# XMOD.net
KiCad netlist of a schematic drawn in Altium Designer
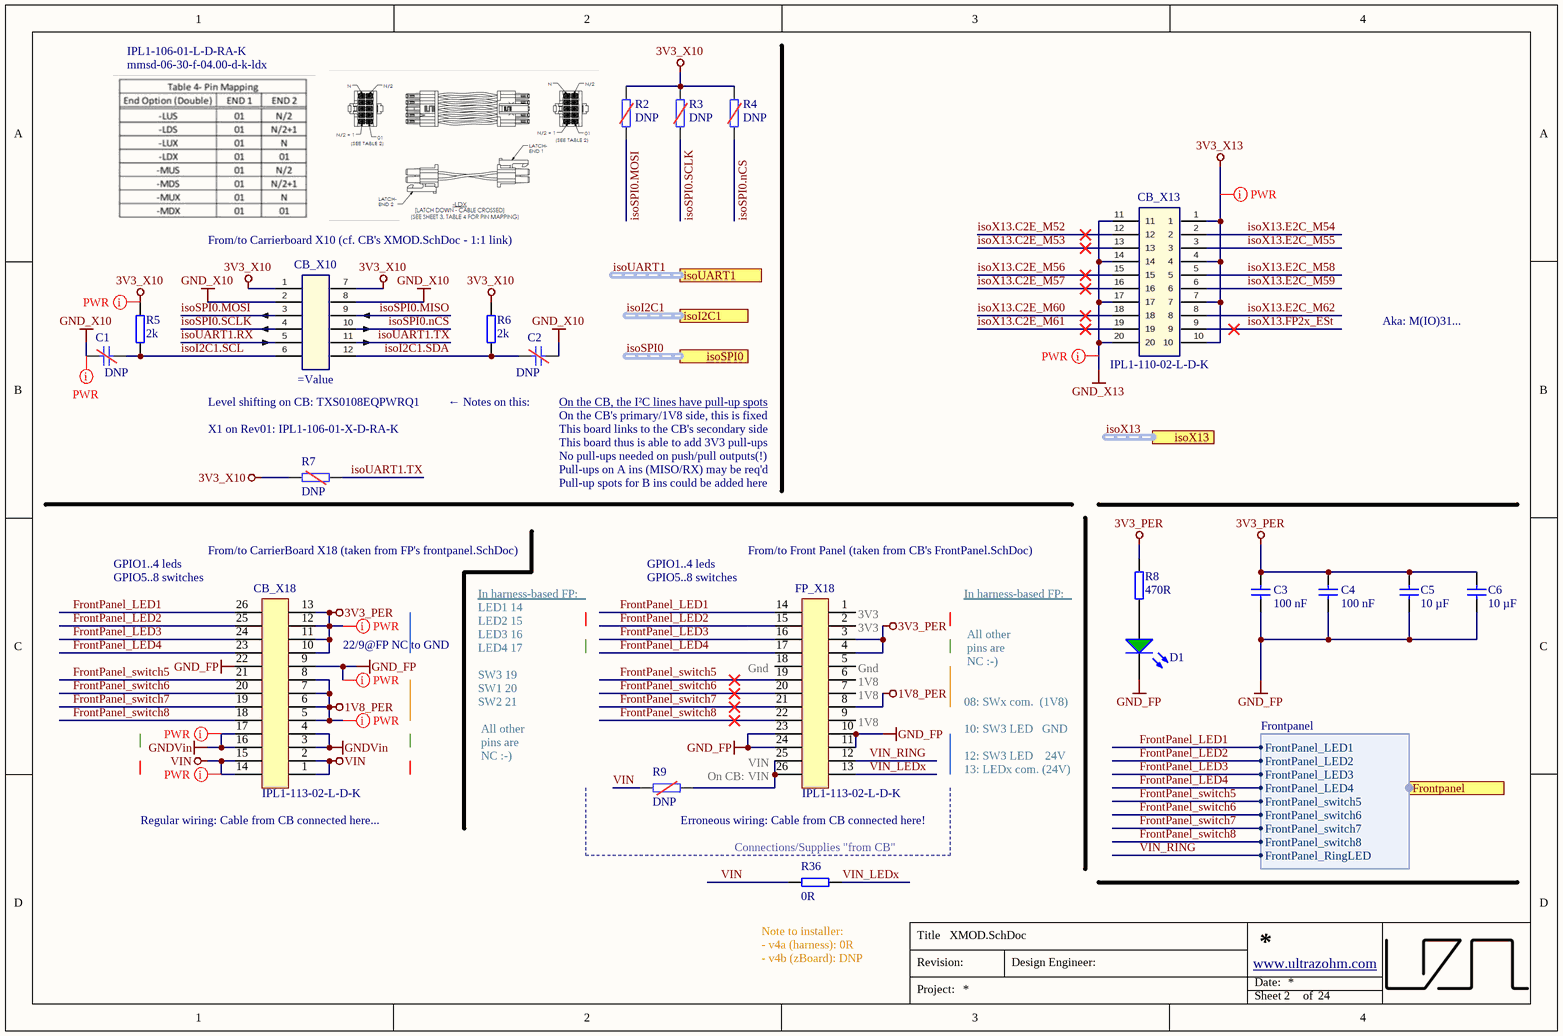
[diagram p0: XMOD.SchDoc]

(export (version "E")
  (design (tool "Eeschema 10.0.6"))
  (components
    (comp (ref "C1")
      (value "DNP")
      (footprint "C_0603_TE-DNP")
      (description "Generic capacitor (DNP)")
      (fields
        (field (name "MANUFACTURER PART NUMBER") "UZgen_C_0603_DNP")
        (field (name "MANUFACTURER") "UZgen")
        (field (name "CREATED FROM") "UZgenTool")
      )
      (libsource (lib "user") (part "CAP-NP-DNP"))
    )
    (comp (ref "C2")
      (value "DNP")
      (footprint "C_0603_TE-DNP")
      (description "Generic capacitor (DNP)")
      (fields
        (field (name "MANUFACTURER PART NUMBER") "UZgen_C_0603_DNP")
        (field (name "MANUFACTURER") "UZgen")
        (field (name "CREATED FROM") "UZgenTool")
      )
      (libsource (lib "user") (part "CAP-NP-DNP"))
    )
    (comp (ref "C3")
      (value "100 nF")
      (footprint "C_0603_TE")
      (description "Generic capacitor")
      (fields
        (field (name "TOLERANCE") "10 %")
        (field (name "MANUFACTURER PART NUMBER") "UZgen_C_0603_100nF_50V_X7R")
        (field (name "CREATED FROM") "AGeiger")
      )
      (libsource (lib "user") (part "CAP-NP"))
    )
    (comp (ref "C4")
      (value "100 nF")
      (footprint "C_0603_TE")
      (description "Generic capacitor")
      (fields
        (field (name "TOLERANCE") "10 %")
        (field (name "MANUFACTURER PART NUMBER") "UZgen_C_0603_100nF_50V_X7R")
        (field (name "CREATED FROM") "AGeiger")
      )
      (libsource (lib "user") (part "CAP-NP"))
    )
    (comp (ref "C5")
      (value "10 µF")
      (footprint "C_1206_TE")
      (description "Generic capacitor")
      (fields
        (field (name "TOLERANCE") "10 %")
        (field (name "VOLTAGE") "50V")
        (field (name "CREATED FROM") "MGeier")
      )
      (libsource (lib "user") (part "CAP-NP"))
    )
    (comp (ref "C6")
      (value "10 µF")
      (footprint "C_1206_TE")
      (description "Generic capacitor")
      (fields
        (field (name "TOLERANCE") "10 %")
        (field (name "VOLTAGE") "50V")
        (field (name "CREATED FROM") "MGeier")
      )
      (libsource (lib "user") (part "CAP-NP"))
    )
    (comp (ref "CB_X10")
      (value "~")
      (footprint "IPL1-106-02-L-D-K")
      (description "Headers & Wire Housings .100\" Mini Mate Isolated Power Terminal Header")
      (fields
        (field (name "MANUFACTURER PART NUMBER") "IPL1-106-02-L-D-K")
        (field (name "MANUFACTURER") "SAMTEC")
        (field (name "CREATED FROM") "AGeiger")
      )
      (libsource (lib "user") (part "IPL1-106-XX-X-D-X"))
    )
    (comp (ref "CB_X13")
      (value "IPL1-110-02-L-D-K")
      (footprint "IPL1-110-02-L-D-K")
      (description "2.54 mm Double Row Termin Assembly (SMD)")
      (fields
        (field (name "MANUFACTURER") "SAMTEC")
        (field (name "LCSC PART NUMBER") "C7544188")
        (field (name "CREATED FROM") "MGremer")
      )
      (libsource (lib "user") (part "IPL1-110-XX-X-D-X"))
    )
    (comp (ref "CB_X18")
      (value "IPL1-113-02-L-D-K")
      (footprint "IPL1-113-02-L-D-K")
      (description "2.54 mm Double Row Termin Assembly (SMD)")
      (fields
        (field (name "MANUFACTURER") "SAMTEC")
        (field (name "LCSC PART NUMBER") "C5290052")
        (field (name "CREATED FROM") "MGremer")
      )
      (libsource (lib "user") (part "IPL1-113-XX-X-D-K"))
    )
    (comp (ref "D1")
      (value "LED Green")
      (footprint "WL-SMCW_0603")
      (description "Standard LEDs - SMD 0603 green")
      (fields
        (field (name "MANUFACTURER PART NUMBER") "UZgen_LED_0603_Green")
        (field (name "MANUFACTURER") "UZgen")
        (field (name "CREATED FROM") "UZgenTool")
      )
      (libsource (lib "user") (part "LED_Green"))
    )
    (comp (ref "FP_X18")
      (value "IPL1-113-02-L-D-K")
      (footprint "IPL1-113-02-L-D-K")
      (description "2.54 mm Double Row Termin Assembly (SMD)")
      (fields
        (field (name "MANUFACTURER") "SAMTEC")
        (field (name "LCSC PART NUMBER") "C5290052")
        (field (name "CREATED FROM") "MGremer")
      )
      (libsource (lib "") (part "IPL1-113-XX-X-D-K_1"))
    )
    (comp (ref "R2")
      (value "DNP")
      (footprint "R_0603_TE-DNP")
      (description "Generic resistor (DNP)")
      (fields
        (field (name "MANUFACTURER PART NUMBER") "UZgen_R_0603_DNP")
        (field (name "MANUFACTURER") "UZgen")
        (field (name "CREATED FROM") "UZgenTool")
      )
      (libsource (lib "user") (part "RES-DNP"))
    )
    (comp (ref "R3")
      (value "DNP")
      (footprint "R_0603_TE-DNP")
      (description "Generic resistor (DNP)")
      (fields
        (field (name "MANUFACTURER PART NUMBER") "UZgen_R_0603_DNP")
        (field (name "MANUFACTURER") "UZgen")
        (field (name "CREATED FROM") "UZgenTool")
      )
      (libsource (lib "user") (part "RES-DNP"))
    )
    (comp (ref "R4")
      (value "DNP")
      (footprint "R_0603_TE-DNP")
      (description "Generic resistor (DNP)")
      (fields
        (field (name "MANUFACTURER PART NUMBER") "UZgen_R_0603_DNP")
        (field (name "MANUFACTURER") "UZgen")
        (field (name "CREATED FROM") "UZgenTool")
      )
      (libsource (lib "user") (part "RES-DNP"))
    )
    (comp (ref "R5")
      (value "2k")
      (footprint "R_0603_TE")
      (description "Generic resistor")
      (fields
        (field (name "TOLERANCE") "1 %")
        (field (name "MANUFACTURER PART NUMBER") "UZgen_R_0603_2k")
        (field (name "CREATED FROM") "UZgenTool")
      )
      (libsource (lib "user") (part "RES"))
    )
    (comp (ref "R6")
      (value "2k")
      (footprint "R_0603_TE")
      (description "Generic resistor")
      (fields
        (field (name "TOLERANCE") "1 %")
        (field (name "MANUFACTURER PART NUMBER") "UZgen_R_0603_2k")
        (field (name "CREATED FROM") "UZgenTool")
      )
      (libsource (lib "user") (part "RES"))
    )
    (comp (ref "R7")
      (value "DNP")
      (footprint "R_0603_TE-DNP")
      (description "Generic resistor (DNP)")
      (fields
        (field (name "MANUFACTURER PART NUMBER") "UZgen_R_0603_DNP")
        (field (name "MANUFACTURER") "UZgen")
        (field (name "CREATED FROM") "UZgenTool")
      )
      (libsource (lib "user") (part "RES-DNP"))
    )
    (comp (ref "R8")
      (value "470R")
      (footprint "R_0603_TE")
      (description "Generic resistor")
      (fields
        (field (name "TOLERANCE") "1 %")
        (field (name "MANUFACTURER PART NUMBER") "UZgen_R_0603_470R")
        (field (name "CREATED FROM") "UZgenTool")
      )
      (libsource (lib "user") (part "RES"))
    )
    (comp (ref "R9")
      (value "DNP")
      (footprint "R_0603_TE-DNP")
      (description "Generic resistor (DNP)")
      (fields
        (field (name "MANUFACTURER PART NUMBER") "UZgen_R_0603_DNP")
        (field (name "MANUFACTURER") "UZgen")
        (field (name "CREATED FROM") "UZgenTool")
      )
      (libsource (lib "user") (part "RES-DNP"))
    )
    (comp (ref "R36")
      (value "0R")
      (footprint "R_0603_TE")
      (description "Generic resistor")
      (fields
        (field (name "TOLERANCE") "1 %")
        (field (name "MANUFACTURER PART NUMBER") "UZgen_R_0603_0R")
        (field (name "CREATED FROM") "UZgenTool")
      )
      (libsource (lib "user") (part "RES"))
    )
  )
  (nets
    (net (code "6") (name "/FrontPanel_LED1") (class "Default")
      (node (ref "CB_X18") (pin "26") (pinfunction "26_26") (pintype "passive"))
      (node (ref "FP_X18") (pin "14") (pinfunction "14_14") (pintype "passive"))
    )
    (net (code "7") (name "/FrontPanel_LED2") (class "Default")
      (node (ref "CB_X18") (pin "25") (pinfunction "25_25") (pintype "passive"))
      (node (ref "FP_X18") (pin "15") (pinfunction "15_15") (pintype "passive"))
    )
    (net (code "8") (name "/FrontPanel_LED3") (class "Default")
      (node (ref "CB_X18") (pin "24") (pinfunction "24_24") (pintype "passive"))
      (node (ref "FP_X18") (pin "16") (pinfunction "16_16") (pintype "passive"))
    )
    (net (code "9") (name "/FrontPanel_LED4") (class "Default")
      (node (ref "CB_X18") (pin "23") (pinfunction "23_23") (pintype "passive"))
      (node (ref "FP_X18") (pin "17") (pinfunction "17_17") (pintype "passive"))
    )
    (net (code "10") (name "/FrontPanel_switch5") (class "Default")
      (node (ref "CB_X18") (pin "21") (pinfunction "21_21") (pintype "passive"))
      (node (ref "FP_X18") (pin "19") (pinfunction "19_19") (pintype "passive"))
    )
    (net (code "11") (name "/FrontPanel_switch6") (class "Default")
      (node (ref "CB_X18") (pin "20") (pinfunction "20_20") (pintype "passive"))
      (node (ref "FP_X18") (pin "20") (pinfunction "20_20") (pintype "passive"))
    )
    (net (code "12") (name "/FrontPanel_switch7") (class "Default")
      (node (ref "CB_X18") (pin "19") (pinfunction "19_19") (pintype "passive"))
      (node (ref "FP_X18") (pin "21") (pinfunction "21_21") (pintype "passive"))
    )
    (net (code "13") (name "/FrontPanel_switch8") (class "Default")
      (node (ref "CB_X18") (pin "18") (pinfunction "18_18") (pintype "passive"))
      (node (ref "FP_X18") (pin "22") (pinfunction "22_22") (pintype "passive"))
    )
    (net (code "14") (name "/VIN_LEDx") (class "Default")
      (node (ref "FP_X18") (pin "13") (pinfunction "13_13") (pintype "passive"))
      (node (ref "R36") (pin "2") (pinfunction "2_2") (pintype "passive"))
    )
    (net (code "15") (name "/VIN_RING") (class "Default")
      (node (ref "FP_X18") (pin "12") (pinfunction "12_12") (pintype "passive"))
    )
    (net (code "16") (name "/isoI2C1.SCL") (class "Default")
      (node (ref "C1") (pin "2") (pinfunction "2_2") (pintype "passive"))
      (node (ref "CB_X10") (pin "6") (pinfunction "6_6") (pintype "passive"))
      (node (ref "R5") (pin "1") (pinfunction "1_1") (pintype "passive"))
    )
    (net (code "17") (name "/isoI2C1.SDA") (class "Default")
      (node (ref "C2") (pin "1") (pinfunction "1_1") (pintype "passive"))
      (node (ref "CB_X10") (pin "12") (pinfunction "12_12") (pintype "passive"))
      (node (ref "R6") (pin "1") (pinfunction "1_1") (pintype "passive"))
    )
    (net (code "18") (name "/isoSPI0.MISO") (class "Default")
      (node (ref "CB_X10") (pin "9") (pinfunction "9_9") (pintype "passive"))
    )
    (net (code "19") (name "/isoSPI0.MOSI") (class "Default")
      (node (ref "CB_X10") (pin "3") (pinfunction "3_3") (pintype "passive"))
      (node (ref "R2") (pin "1") (pinfunction "1_1") (pintype "passive"))
    )
    (net (code "20") (name "/isoSPI0.SCLK") (class "Default")
      (node (ref "CB_X10") (pin "4") (pinfunction "4_4") (pintype "passive"))
      (node (ref "R3") (pin "1") (pinfunction "1_1") (pintype "passive"))
    )
    (net (code "21") (name "/isoSPI0.nCS") (class "Default")
      (node (ref "CB_X10") (pin "10") (pinfunction "10_10") (pintype "passive"))
      (node (ref "R4") (pin "1") (pinfunction "1_1") (pintype "passive"))
    )
    (net (code "22") (name "/isoUART1.RX") (class "Default")
      (node (ref "CB_X10") (pin "5") (pinfunction "5_5") (pintype "passive"))
    )
    (net (code "23") (name "/isoUART1.TX") (class "Default")
      (node (ref "CB_X10") (pin "11") (pinfunction "11_11") (pintype "passive"))
      (node (ref "R7") (pin "1") (pinfunction "1_1") (pintype "passive"))
    )
    (net (code "24") (name "/isoX13.C2E_M52") (class "Default")
      (node (ref "CB_X13") (pin "12") (pinfunction "12_12") (pintype "passive"))
    )
    (net (code "25") (name "/isoX13.C2E_M53") (class "Default")
      (node (ref "CB_X13") (pin "13") (pinfunction "13_13") (pintype "passive"))
    )
    (net (code "26") (name "/isoX13.C2E_M56") (class "Default")
      (node (ref "CB_X13") (pin "15") (pinfunction "15_15") (pintype "passive"))
    )
    (net (code "27") (name "/isoX13.C2E_M57") (class "Default")
      (node (ref "CB_X13") (pin "16") (pinfunction "16_16") (pintype "passive"))
    )
    (net (code "28") (name "/isoX13.C2E_M60") (class "Default")
      (node (ref "CB_X13") (pin "18") (pinfunction "18_18") (pintype "passive"))
    )
    (net (code "29") (name "/isoX13.C2E_M61") (class "Default")
      (node (ref "CB_X13") (pin "19") (pinfunction "19_19") (pintype "passive"))
    )
    (net (code "30") (name "/isoX13.E2C_M54") (class "Default")
      (node (ref "CB_X13") (pin "2") (pinfunction "2_2") (pintype "passive"))
    )
    (net (code "31") (name "/isoX13.E2C_M55") (class "Default")
      (node (ref "CB_X13") (pin "3") (pinfunction "3_3") (pintype "passive"))
    )
    (net (code "32") (name "/isoX13.E2C_M58") (class "Default")
      (node (ref "CB_X13") (pin "5") (pinfunction "5_5") (pintype "passive"))
    )
    (net (code "33") (name "/isoX13.E2C_M59") (class "Default")
      (node (ref "CB_X13") (pin "6") (pinfunction "6_6") (pintype "passive"))
    )
    (net (code "34") (name "/isoX13.E2C_M62") (class "Default")
      (node (ref "CB_X13") (pin "8") (pinfunction "8_8") (pintype "passive"))
    )
    (net (code "35") (name "/isoX13.FP2x_ESt") (class "Default")
      (node (ref "CB_X13") (pin "9") (pinfunction "9_9") (pintype "passive"))
    )
    (net (code "41") (name "1V8_PER") (class "Default")
      (node (ref "CB_X18") (pin "5") (pinfunction "5_5") (pintype "passive"))
      (node (ref "CB_X18") (pin "6") (pinfunction "6_6") (pintype "passive"))
      (node (ref "CB_X18") (pin "7") (pinfunction "7_7") (pintype "passive"))
      (node (ref "CB_X18") (pin "8") (pinfunction "8_8") (pintype "passive"))
      (node (ref "FP_X18") (pin "8") (pinfunction "8_8") (pintype "passive"))
    )
    (net (code "42") (name "3V3_PER") (class "Default")
      (node (ref "C3") (pin "1") (pinfunction "1_1") (pintype "passive"))
      (node (ref "C4") (pin "1") (pinfunction "1_1") (pintype "passive"))
      (node (ref "C5") (pin "2") (pinfunction "2_2") (pintype "passive"))
      (node (ref "C6") (pin "2") (pinfunction "2_2") (pintype "passive"))
      (node (ref "CB_X18") (pin "10") (pinfunction "10_10") (pintype "passive"))
      (node (ref "CB_X18") (pin "11") (pinfunction "11_11") (pintype "passive"))
      (node (ref "CB_X18") (pin "12") (pinfunction "12_12") (pintype "passive"))
      (node (ref "CB_X18") (pin "13") (pinfunction "13_13") (pintype "passive"))
      (node (ref "FP_X18") (pin "3") (pinfunction "3_3") (pintype "passive"))
      (node (ref "FP_X18") (pin "4") (pinfunction "4_4") (pintype "passive"))
      (node (ref "R8") (pin "2") (pinfunction "2_2") (pintype "passive"))
    )
    (net (code "43") (name "3V3_X10") (class "Default")
      (node (ref "CB_X10") (pin "1") (pinfunction "1_1") (pintype "passive"))
      (node (ref "CB_X10") (pin "7") (pinfunction "7_7") (pintype "passive"))
      (node (ref "R2") (pin "2") (pinfunction "2_2") (pintype "passive"))
      (node (ref "R3") (pin "2") (pinfunction "2_2") (pintype "passive"))
      (node (ref "R4") (pin "2") (pinfunction "2_2") (pintype "passive"))
      (node (ref "R5") (pin "2") (pinfunction "2_2") (pintype "passive"))
      (node (ref "R6") (pin "2") (pinfunction "2_2") (pintype "passive"))
      (node (ref "R7") (pin "2") (pinfunction "2_2") (pintype "passive"))
    )
    (net (code "44") (name "3V3_X13") (class "Default")
      (node (ref "CB_X13") (pin "1") (pinfunction "1_1") (pintype "passive"))
      (node (ref "CB_X13") (pin "10") (pinfunction "10_10") (pintype "passive"))
      (node (ref "CB_X13") (pin "4") (pinfunction "4_4") (pintype "passive"))
      (node (ref "CB_X13") (pin "7") (pinfunction "7_7") (pintype "passive"))
    )
    (net (code "45") (name "GNDVin") (class "Default")
      (node (ref "CB_X18") (pin "16") (pinfunction "16_16") (pintype "passive"))
      (node (ref "CB_X18") (pin "17") (pinfunction "17_17") (pintype "passive"))
      (node (ref "CB_X18") (pin "3") (pinfunction "3_3") (pintype "passive"))
      (node (ref "CB_X18") (pin "4") (pinfunction "4_4") (pintype "passive"))
    )
    (net (code "46") (name "GND_FP") (class "Default")
      (node (ref "C3") (pin "2") (pinfunction "2_2") (pintype "passive"))
      (node (ref "C4") (pin "2") (pinfunction "2_2") (pintype "passive"))
      (node (ref "C5") (pin "1") (pinfunction "1_1") (pintype "passive"))
      (node (ref "C6") (pin "1") (pinfunction "1_1") (pintype "passive"))
      (node (ref "CB_X18") (pin "22") (pinfunction "22_22") (pintype "passive"))
      (node (ref "CB_X18") (pin "9") (pinfunction "9_9") (pintype "passive"))
      (node (ref "D1") (pin "1") (pinfunction "K_1") (pintype "passive"))
      (node (ref "FP_X18") (pin "10") (pinfunction "10_10") (pintype "passive"))
      (node (ref "FP_X18") (pin "11") (pinfunction "11_11") (pintype "passive"))
      (node (ref "FP_X18") (pin "23") (pinfunction "23_23") (pintype "passive"))
      (node (ref "FP_X18") (pin "24") (pinfunction "24_24") (pintype "passive"))
    )
    (net (code "47") (name "GND_X10") (class "Default")
      (node (ref "C1") (pin "1") (pinfunction "1_1") (pintype "passive"))
      (node (ref "C2") (pin "2") (pinfunction "2_2") (pintype "passive"))
      (node (ref "CB_X10") (pin "2") (pinfunction "2_2") (pintype "passive"))
      (node (ref "CB_X10") (pin "8") (pinfunction "8_8") (pintype "passive"))
    )
    (net (code "48") (name "GND_X13") (class "Default")
      (node (ref "CB_X13") (pin "11") (pinfunction "11_11") (pintype "passive"))
      (node (ref "CB_X13") (pin "14") (pinfunction "14_14") (pintype "passive"))
      (node (ref "CB_X13") (pin "17") (pinfunction "17_17") (pintype "passive"))
      (node (ref "CB_X13") (pin "20") (pinfunction "20_20") (pintype "passive"))
    )
    (net (code "49") (name "Net-(D1-A)") (class "Default")
      (node (ref "D1") (pin "2") (pinfunction "A_2") (pintype "passive"))
      (node (ref "R8") (pin "1") (pinfunction "1_1") (pintype "passive"))
    )
    (net (code "50") (name "Net-(FP_X18-Pad25)") (class "Default")
      (node (ref "FP_X18") (pin "25") (pinfunction "25_25") (pintype "passive"))
      (node (ref "FP_X18") (pin "26") (pinfunction "26_26") (pintype "passive"))
      (node (ref "R9") (pin "2") (pinfunction "2_2") (pintype "passive"))
    )
    (net (code "51") (name "VIN") (class "Default")
      (node (ref "CB_X18") (pin "1") (pinfunction "1_1") (pintype "passive"))
      (node (ref "CB_X18") (pin "14") (pinfunction "14_14") (pintype "passive"))
      (node (ref "CB_X18") (pin "15") (pinfunction "15_15") (pintype "passive"))
      (node (ref "CB_X18") (pin "2") (pinfunction "2_2") (pintype "passive"))
      (node (ref "R36") (pin "1") (pinfunction "1_1") (pintype "passive"))
      (node (ref "R9") (pin "1") (pinfunction "1_1") (pintype "passive"))
    )
    (net (code "52") (name "unconnected-(FP_X18-Pad1)") (class "Default")
      (node (ref "FP_X18") (pin "1") (pinfunction "1_1") (pintype "passive"))
    )
    (net (code "53") (name "unconnected-(FP_X18-Pad2)") (class "Default")
      (node (ref "FP_X18") (pin "2") (pinfunction "2_2") (pintype "passive"))
    )
    (net (code "54") (name "unconnected-(FP_X18-Pad5)") (class "Default")
      (node (ref "FP_X18") (pin "5") (pinfunction "5_5") (pintype "passive"))
    )
    (net (code "55") (name "unconnected-(FP_X18-Pad6)") (class "Default")
      (node (ref "FP_X18") (pin "6") (pinfunction "6_6") (pintype "passive"))
    )
    (net (code "56") (name "unconnected-(FP_X18-Pad7)") (class "Default")
      (node (ref "FP_X18") (pin "7") (pinfunction "7_7") (pintype "passive"))
    )
    (net (code "57") (name "unconnected-(FP_X18-Pad9)") (class "Default")
      (node (ref "FP_X18") (pin "9") (pinfunction "9_9") (pintype "passive"))
    )
    (net (code "58") (name "unconnected-(FP_X18-Pad18)") (class "Default")
      (node (ref "FP_X18") (pin "18") (pinfunction "18_18") (pintype "passive"))
    )
  )
)
